# SecBadge.net
KiCad netlist of a schematic drawn in EAGLE
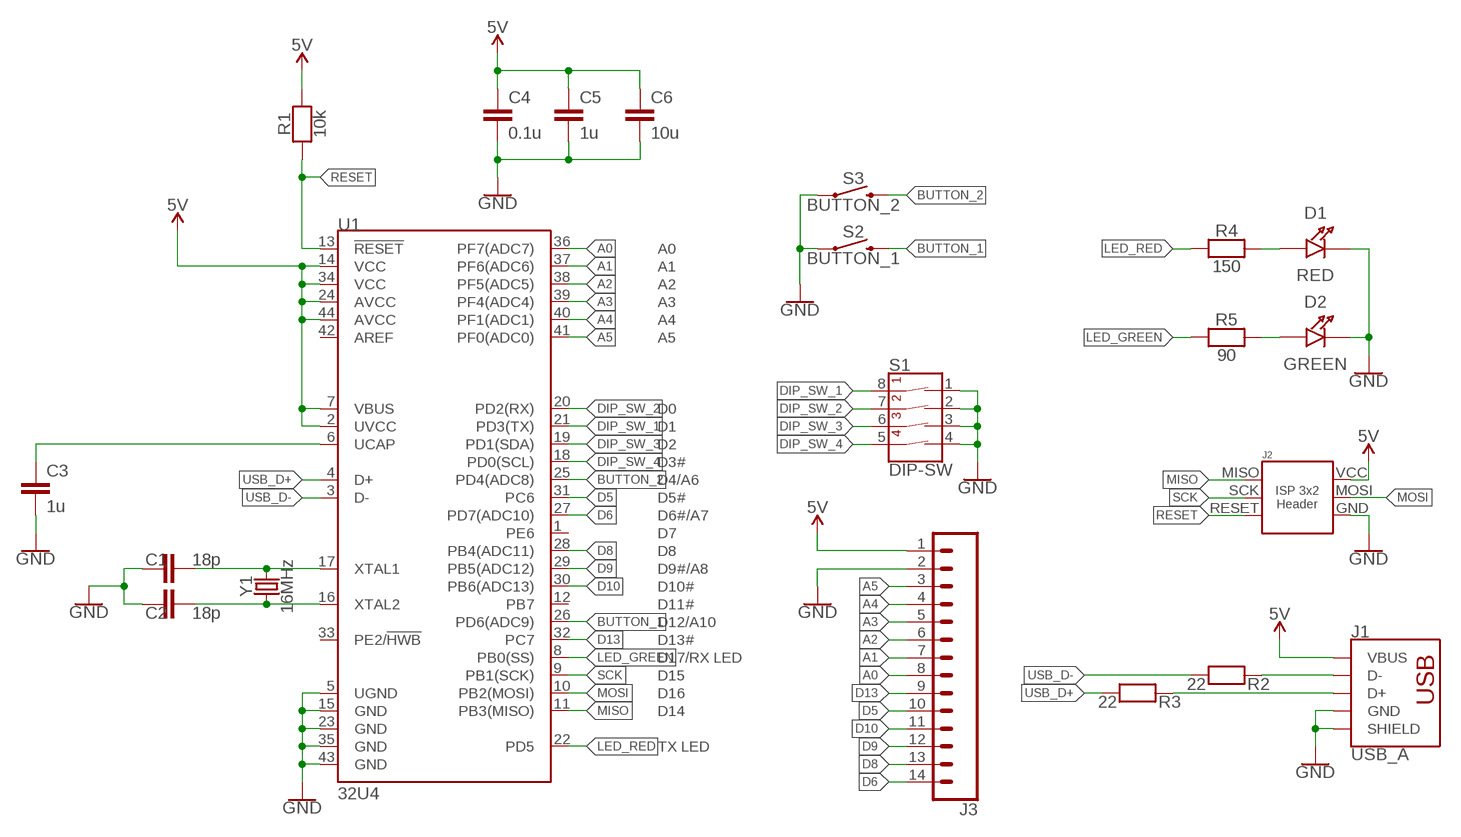
[diagram p0: schematic, sheet 1]

(export (version "E")
  (design (tool "Eeschema 10.0.6"))
  (components
    (comp (ref "C1")
      (value "18p")
      (footprint "eagle-import:1206")
      (libsource (lib "eagle-import") (part "CAPACITOR1206"))
    )
    (comp (ref "C2")
      (value "18p")
      (footprint "eagle-import:1206")
      (libsource (lib "eagle-import") (part "CAPACITOR1206"))
    )
    (comp (ref "C3")
      (value "1u")
      (footprint "eagle-import:1206")
      (libsource (lib "eagle-import") (part "CAPACITOR1206"))
    )
    (comp (ref "C4")
      (value "0.1u")
      (footprint "eagle-import:1206")
      (libsource (lib "eagle-import") (part "CAPACITOR1206"))
    )
    (comp (ref "C5")
      (value "1u")
      (footprint "eagle-import:1206")
      (libsource (lib "eagle-import") (part "CAPACITOR1206"))
    )
    (comp (ref "C6")
      (value "10u")
      (footprint "eagle-import:1206")
      (libsource (lib "eagle-import") (part "CAPACITOR1206"))
    )
    (comp (ref "D1")
      (value "RED")
      (footprint "eagle-import:LED-1206")
      (libsource (lib "eagle-import") (part "LED"))
    )
    (comp (ref "D2")
      (value "GREEN")
      (footprint "eagle-import:LED-1206")
      (libsource (lib "eagle-import") (part "LED"))
    )
    (comp (ref "J1")
      (value "USB_A")
      (footprint "eagle-import:USB_A_MALE_THT")
      (libsource (lib "eagle-import") (part "USB_A"))
    )
    (comp (ref "J2")
      (value "AVR_ISP_PROG_3X2")
      (footprint "eagle-import:3X2_NO_SILK")
      (libsource (lib "eagle-import") (part "AVR_ISP_PROG_3X2"))
    )
    (comp (ref "J3")
      (value "CONN_14")
      (footprint "eagle-import:1X14")
      (libsource (lib "eagle-import") (part "CONN_14"))
    )
    (comp (ref "R1")
      (value "10k")
      (footprint "eagle-import:1206")
      (libsource (lib "eagle-import") (part "RESISTOR1206"))
    )
    (comp (ref "R2")
      (value "22")
      (footprint "eagle-import:1206")
      (libsource (lib "eagle-import") (part "RESISTOR1206"))
    )
    (comp (ref "R3")
      (value "22")
      (footprint "eagle-import:1206")
      (libsource (lib "eagle-import") (part "RESISTOR1206"))
    )
    (comp (ref "R4")
      (value "150")
      (footprint "eagle-import:1206")
      (libsource (lib "eagle-import") (part "RESISTOR1206"))
    )
    (comp (ref "R5")
      (value "90")
      (footprint "eagle-import:1206")
      (libsource (lib "eagle-import") (part "RESISTOR1206"))
    )
    (comp (ref "S1")
      (value "DIP-SW")
      (footprint "eagle-import:DIP8")
      (libsource (lib "eagle-import") (part "DIP-SW-4POSPHT"))
    )
    (comp (ref "S2")
      (value "BUTTON_1")
      (footprint "eagle-import:TACTILE_SWITCH_PTH_6.0MM")
      (libsource (lib "eagle-import") (part "MOMENTARY-SWITCH-SPST-PTH-6.0MM"))
    )
    (comp (ref "S3")
      (value "BUTTON_2")
      (footprint "eagle-import:TACTILE_SWITCH_PTH_6.0MM")
      (libsource (lib "eagle-import") (part "MOMENTARY-SWITCH-SPST-PTH-6.0MM"))
    )
    (comp (ref "U1")
      (value "32U4")
      (footprint "eagle-import:TQFP44")
      (libsource (lib "eagle-import") (part "ATMEGA32U4TQFP-44"))
    )
    (comp (ref "Y1")
      (value "16MHz")
      (footprint "eagle-import:HC49UP")
      (libsource (lib "eagle-import") (part "CRYSTALSMD-HC49UP"))
    )
  )
  (nets
    (net (code "1") (name "5V") (class "Default")
      (node (ref "C4") (pin "1") (pinfunction "1_1") (pintype "passive"))
      (node (ref "C5") (pin "1") (pinfunction "1_1") (pintype "passive"))
      (node (ref "C6") (pin "1") (pinfunction "1_1") (pintype "passive"))
      (node (ref "J1") (pin "VBUS") (pinfunction "VBUS_VBUS") (pintype "power_in"))
      (node (ref "J2") (pin "VCC") (pinfunction "VCC_VCC") (pintype "power_in"))
      (node (ref "J3") (pin "1") (pinfunction "1_1") (pintype "passive"))
      (node (ref "R1") (pin "1") (pinfunction "P$1_1") (pintype "passive"))
      (node (ref "U1") (pin "14") (pinfunction "VCC_14") (pintype "bidirectional"))
      (node (ref "U1") (pin "2") (pinfunction "UVCC_2") (pintype "bidirectional"))
      (node (ref "U1") (pin "24") (pinfunction "AVCC_24") (pintype "bidirectional"))
      (node (ref "U1") (pin "34") (pinfunction "VCC_34") (pintype "bidirectional"))
      (node (ref "U1") (pin "44") (pinfunction "AVCC_44") (pintype "bidirectional"))
      (node (ref "U1") (pin "7") (pinfunction "VBUS_7") (pintype "bidirectional"))
    )
    (net (code "2") (name "A0") (class "Default")
      (node (ref "J3") (pin "8") (pinfunction "8_8") (pintype "passive"))
      (node (ref "U1") (pin "36") (pinfunction "PF7(ADC7)_36") (pintype "bidirectional"))
    )
    (net (code "3") (name "A1") (class "Default")
      (node (ref "J3") (pin "7") (pinfunction "7_7") (pintype "passive"))
      (node (ref "U1") (pin "37") (pinfunction "PF6(ADC6)_37") (pintype "bidirectional"))
    )
    (net (code "4") (name "A2") (class "Default")
      (node (ref "J3") (pin "6") (pinfunction "6_6") (pintype "passive"))
      (node (ref "U1") (pin "38") (pinfunction "PF5(ADC5)_38") (pintype "bidirectional"))
    )
    (net (code "5") (name "A3") (class "Default")
      (node (ref "J3") (pin "5") (pinfunction "5_5") (pintype "passive"))
      (node (ref "U1") (pin "39") (pinfunction "PF4(ADC4)_39") (pintype "bidirectional"))
    )
    (net (code "6") (name "A4") (class "Default")
      (node (ref "J3") (pin "4") (pinfunction "4_4") (pintype "passive"))
      (node (ref "U1") (pin "40") (pinfunction "PF1(ADC1)_40") (pintype "bidirectional"))
    )
    (net (code "7") (name "A5") (class "Default")
      (node (ref "J3") (pin "3") (pinfunction "3_3") (pintype "passive"))
      (node (ref "U1") (pin "41") (pinfunction "PF0(ADC0)_41") (pintype "bidirectional"))
    )
    (net (code "8") (name "BUTTON_1") (class "Default")
      (node (ref "S2") (pin "3") (pinfunction "2_3") (pintype "passive"))
      (node (ref "U1") (pin "26") (pinfunction "PD6(ADC9)_26") (pintype "bidirectional"))
    )
    (net (code "9") (name "BUTTON_2") (class "Default")
      (node (ref "S3") (pin "3") (pinfunction "2_3") (pintype "passive"))
      (node (ref "U1") (pin "25") (pinfunction "PD4(ADC8)_25") (pintype "bidirectional"))
    )
    (net (code "10") (name "D5") (class "Default")
      (node (ref "J3") (pin "10") (pinfunction "10_10") (pintype "passive"))
      (node (ref "U1") (pin "31") (pinfunction "PC6_31") (pintype "bidirectional"))
    )
    (net (code "11") (name "D6") (class "Default")
      (node (ref "J3") (pin "14") (pinfunction "14_14") (pintype "passive"))
      (node (ref "U1") (pin "27") (pinfunction "PD7(ADC10)_27") (pintype "bidirectional"))
    )
    (net (code "12") (name "D8") (class "Default")
      (node (ref "J3") (pin "13") (pinfunction "13_13") (pintype "passive"))
      (node (ref "U1") (pin "28") (pinfunction "PB4(ADC11)_28") (pintype "bidirectional"))
    )
    (net (code "13") (name "D9") (class "Default")
      (node (ref "J3") (pin "12") (pinfunction "12_12") (pintype "passive"))
      (node (ref "U1") (pin "29") (pinfunction "PB5(ADC12)_29") (pintype "bidirectional"))
    )
    (net (code "14") (name "D10") (class "Default")
      (node (ref "J3") (pin "11") (pinfunction "11_11") (pintype "passive"))
      (node (ref "U1") (pin "30") (pinfunction "PB6(ADC13)_30") (pintype "bidirectional"))
    )
    (net (code "15") (name "D13") (class "Default")
      (node (ref "J3") (pin "9") (pinfunction "9_9") (pintype "passive"))
      (node (ref "U1") (pin "32") (pinfunction "PC7_32") (pintype "bidirectional"))
    )
    (net (code "16") (name "DIP_SW_1") (class "Default")
      (node (ref "S1") (pin "8") (pinfunction "1B_8") (pintype "bidirectional"))
      (node (ref "U1") (pin "21") (pinfunction "PD3(TX)_21") (pintype "bidirectional"))
    )
    (net (code "17") (name "DIP_SW_2") (class "Default")
      (node (ref "S1") (pin "7") (pinfunction "2B_7") (pintype "bidirectional"))
      (node (ref "U1") (pin "20") (pinfunction "PD2(RX)_20") (pintype "bidirectional"))
    )
    (net (code "18") (name "DIP_SW_3") (class "Default")
      (node (ref "S1") (pin "6") (pinfunction "3B_6") (pintype "bidirectional"))
      (node (ref "U1") (pin "19") (pinfunction "PD1(SDA)_19") (pintype "bidirectional"))
    )
    (net (code "19") (name "DIP_SW_4") (class "Default")
      (node (ref "S1") (pin "5") (pinfunction "4B_5") (pintype "bidirectional"))
      (node (ref "U1") (pin "18") (pinfunction "PD0(SCL)_18") (pintype "bidirectional"))
    )
    (net (code "20") (name "GND") (class "Default")
      (node (ref "C1") (pin "1") (pinfunction "1_1") (pintype "passive"))
      (node (ref "C2") (pin "1") (pinfunction "1_1") (pintype "passive"))
      (node (ref "C3") (pin "2") (pinfunction "2_2") (pintype "passive"))
      (node (ref "C4") (pin "2") (pinfunction "2_2") (pintype "passive"))
      (node (ref "C5") (pin "2") (pinfunction "2_2") (pintype "passive"))
      (node (ref "C6") (pin "2") (pinfunction "2_2") (pintype "passive"))
      (node (ref "D1") (pin "C") (pinfunction "CATHODE_C") (pintype "passive"))
      (node (ref "D2") (pin "C") (pinfunction "CATHODE_C") (pintype "passive"))
      (node (ref "J1") (pin "GND") (pinfunction "GND_GND") (pintype "power_in"))
      (node (ref "J1") (pin "SHIELD1") (pinfunction "SHIELD_SHIELD1") (pintype "bidirectional"))
      (node (ref "J1") (pin "SHIELD2") (pinfunction "SHIELD_SHIELD2") (pintype "bidirectional"))
      (node (ref "J2") (pin "GND") (pinfunction "GND_GND") (pintype "power_in"))
      (node (ref "J3") (pin "2") (pinfunction "2_2") (pintype "passive"))
      (node (ref "S1") (pin "1") (pinfunction "1A_1") (pintype "bidirectional"))
      (node (ref "S1") (pin "2") (pinfunction "2A_2") (pintype "bidirectional"))
      (node (ref "S1") (pin "3") (pinfunction "3A_3") (pintype "bidirectional"))
      (node (ref "S1") (pin "4") (pinfunction "4A_4") (pintype "bidirectional"))
      (node (ref "S2") (pin "1") (pinfunction "1_1") (pintype "passive"))
      (node (ref "S3") (pin "1") (pinfunction "1_1") (pintype "passive"))
      (node (ref "U1") (pin "15") (pinfunction "GND_15") (pintype "bidirectional"))
      (node (ref "U1") (pin "23") (pinfunction "GND_23") (pintype "bidirectional"))
      (node (ref "U1") (pin "35") (pinfunction "GND_35") (pintype "bidirectional"))
      (node (ref "U1") (pin "43") (pinfunction "GND_43") (pintype "bidirectional"))
      (node (ref "U1") (pin "5") (pinfunction "UGND_5") (pintype "bidirectional"))
    )
    (net (code "21") (name "LED_GREEN") (class "Default")
      (node (ref "R5") (pin "2") (pinfunction "P$2_2") (pintype "passive"))
      (node (ref "U1") (pin "8") (pinfunction "PB0(SS)_8") (pintype "bidirectional"))
    )
    (net (code "22") (name "LED_RED") (class "Default")
      (node (ref "R4") (pin "2") (pinfunction "P$2_2") (pintype "passive"))
      (node (ref "U1") (pin "22") (pinfunction "PD5_22") (pintype "bidirectional"))
    )
    (net (code "23") (name "MISO") (class "Default")
      (node (ref "J2") (pin "MISO") (pinfunction "MISO_MISO") (pintype "bidirectional"))
      (node (ref "U1") (pin "11") (pinfunction "PB3(MISO)_11") (pintype "bidirectional"))
    )
    (net (code "24") (name "MOSI") (class "Default")
      (node (ref "J2") (pin "MOSI") (pinfunction "MOSI_MOSI") (pintype "bidirectional"))
      (node (ref "U1") (pin "10") (pinfunction "PB2(MOSI)_10") (pintype "bidirectional"))
    )
    (net (code "25") (name "Net-(D1-ANODE)") (class "Default")
      (node (ref "D1") (pin "A") (pinfunction "ANODE_A") (pintype "passive"))
      (node (ref "R4") (pin "1") (pinfunction "P$1_1") (pintype "passive"))
    )
    (net (code "26") (name "Net-(D2-ANODE)") (class "Default")
      (node (ref "D2") (pin "A") (pinfunction "ANODE_A") (pintype "passive"))
      (node (ref "R5") (pin "1") (pinfunction "P$1_1") (pintype "passive"))
    )
    (net (code "27") (name "Net-(R2-P$2)") (class "Default")
      (node (ref "J1") (pin "D-") (pinfunction "D-_D-") (pintype "bidirectional"))
      (node (ref "R2") (pin "2") (pinfunction "P$2_2") (pintype "passive"))
    )
    (net (code "28") (name "Net-(R3-P$2)") (class "Default")
      (node (ref "J1") (pin "D+") (pinfunction "D+_D+") (pintype "bidirectional"))
      (node (ref "R3") (pin "2") (pinfunction "P$2_2") (pintype "passive"))
    )
    (net (code "29") (name "Net-(U1-UCAP)") (class "Default")
      (node (ref "C3") (pin "1") (pinfunction "1_1") (pintype "passive"))
      (node (ref "U1") (pin "6") (pinfunction "UCAP_6") (pintype "bidirectional"))
    )
    (net (code "30") (name "Net-(U1-XTAL1)") (class "Default")
      (node (ref "C1") (pin "2") (pinfunction "2_2") (pintype "passive"))
      (node (ref "U1") (pin "17") (pinfunction "XTAL1_17") (pintype "bidirectional"))
      (node (ref "Y1") (pin "2") (pinfunction "2_2") (pintype "passive"))
    )
    (net (code "31") (name "Net-(U1-XTAL2)") (class "Default")
      (node (ref "C2") (pin "2") (pinfunction "2_2") (pintype "passive"))
      (node (ref "U1") (pin "16") (pinfunction "XTAL2_16") (pintype "bidirectional"))
      (node (ref "Y1") (pin "1") (pinfunction "1_1") (pintype "passive"))
    )
    (net (code "32") (name "RESET") (class "Default")
      (node (ref "J2") (pin "RESET") (pinfunction "RESET_RESET") (pintype "input"))
      (node (ref "R1") (pin "2") (pinfunction "P$2_2") (pintype "passive"))
      (node (ref "U1") (pin "13") (pinfunction "~{RESET}_13") (pintype "bidirectional"))
    )
    (net (code "33") (name "SCK") (class "Default")
      (node (ref "J2") (pin "SCK") (pinfunction "SCK_SCK") (pintype "input"))
      (node (ref "U1") (pin "9") (pinfunction "PB1(SCK)_9") (pintype "bidirectional"))
    )
    (net (code "34") (name "USB_D+") (class "Default")
      (node (ref "R3") (pin "1") (pinfunction "P$1_1") (pintype "passive"))
      (node (ref "U1") (pin "4") (pinfunction "D+_4") (pintype "bidirectional"))
    )
    (net (code "35") (name "USB_D-") (class "Default")
      (node (ref "R2") (pin "1") (pinfunction "P$1_1") (pintype "passive"))
      (node (ref "U1") (pin "3") (pinfunction "D-_3") (pintype "bidirectional"))
    )
    (net (code "36") (name "unconnected-(U1-AREF-Pad42)") (class "Default")
      (node (ref "U1") (pin "42") (pinfunction "AREF_42") (pintype "bidirectional"))
    )
    (net (code "37") (name "unconnected-(U1-PB7-Pad12)") (class "Default")
      (node (ref "U1") (pin "12") (pinfunction "PB7_12") (pintype "bidirectional"))
    )
    (net (code "38") (name "unconnected-(U1-PE2{slash}~{HWB}-Pad33)") (class "Default")
      (node (ref "U1") (pin "33") (pinfunction "PE2/~{HWB}_33") (pintype "bidirectional"))
    )
    (net (code "39") (name "unconnected-(U1-PE6-Pad1)") (class "Default")
      (node (ref "U1") (pin "1") (pinfunction "PE6_1") (pintype "bidirectional"))
    )
  )
)
